# OnOffCircuit.net
KiCad netlist of a schematic drawn in Altium Designer
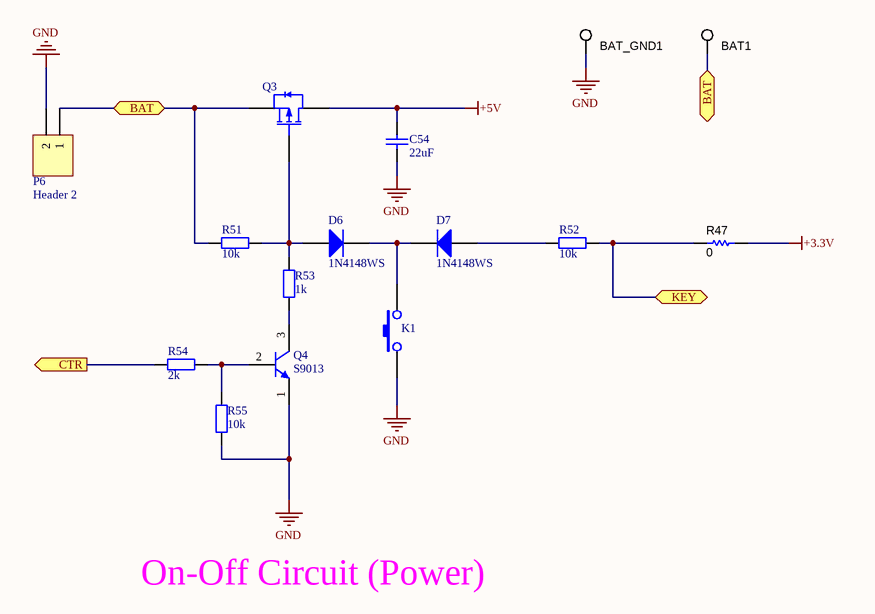
[diagram p0: OnOffCircuit.SchDoc]

(export (version "E")
  (design (tool "Eeschema 10.0.6"))
  (components
    (comp (ref "BAT1")
      (value "5015")
      (footprint "Testpoint_Keystone_Miniature")
      (description "Test Point, Miniature, SMT")
      (fields (field (name "MANUFACTURER") "Keystone") (field (name "PUBLISHER") "Texas Instruments"))
      (libsource (lib "Connectors_Keystone") (part "5015"))
    )
    (comp (ref "BAT_GND1")
      (value "5015")
      (footprint "Testpoint_Keystone_Miniature")
      (description "Test Point, Miniature, SMT")
      (fields (field (name "MANUFACTURER") "Keystone") (field (name "PUBLISHER") "Texas Instruments"))
      (libsource (lib "Connectors_Keystone") (part "5015"))
    )
    (comp (ref "C54")
      (value "22uF")
      (footprint "FDC2214:0603")
      (description "0402贴片电容")
      (libsource (lib "02-Miscellaneous_Devices_ZSF_Library") (part "Cap_0402"))
    )
    (comp (ref "D6")
      (value "1N4148WS")
      (footprint "SOD-323")
      (description "二极管")
      (libsource (lib "02-Miscellaneous_Devices_ZSF_Library") (part "1N4148WS_SOD-323"))
    )
    (comp (ref "D7")
      (value "1N4148WS")
      (footprint "SOD-323")
      (description "二极管")
      (libsource (lib "02-Miscellaneous_Devices_ZSF_Library") (part "1N4148WS_SOD-323"))
    )
    (comp (ref "K1") (value "KEY-2") (footprint "KEY-6*6*9.5") (libsource (lib "KEY") (part "KEY-2")))
    (comp (ref "P6")
      (value "Header 2")
      (footprint "XH254-2")
      (description "Header, 2-Pin")
      (fields (field (name "PUBLISHER") "Altium Limited"))
      (libsource (lib "01-Connect_IntegratedLibrary") (part "Header 2"))
    )
    (comp (ref "Q3")
      (value "AO3401A P道沟 X13A15 SOT-23")
      (footprint "SOT-23-3L")
      (description "MOS(场效应管)")
      (libsource (lib "02-Miscellaneous_Devices_ZSF_Library") (part "AO3401A P道沟 X13A15 SOT-23"))
    )
    (comp (ref "Q4")
      (value "S9013")
      (footprint "SOT-23-3_L2.9-W1.3-P1.90-LS2.4-BR")
      (description "NPN型小功率三极管")
      (libsource (lib "02-Miscellaneous_Devices_ZSF_Library") (part "9013_TO-92"))
    )
    (comp (ref "R47")
      (value "0")
      (footprint "0805_R")
      (description "RES, 0 ohm, 5%, 0.1W, 0603")
      (fields
        (field (name "PARTNUMBER") "CRCW06030000Z0EA")
        (field (name "MANUFACTURER") "Vishay-Dale")
        (field (name "PUBLISHER") "Texas Instruments")
      )
      (libsource (lib "Resistor_0603") (part "CRCW06030000Z0EA"))
    )
    (comp (ref "R51")
      (value "10k")
      (footprint "0805_R")
      (description "0805贴片电阻")
      (libsource (lib "") (part "Res_0805_1"))
    )
    (comp (ref "R52")
      (value "10k")
      (footprint "0805_R")
      (description "0805贴片电阻")
      (libsource (lib "") (part "Res_0805_1"))
    )
    (comp (ref "R53")
      (value "1k")
      (footprint "0805_R")
      (description "0805贴片电阻")
      (libsource (lib "02-Miscellaneous_Devices_ZSF_Library") (part "Res_0805"))
    )
    (comp (ref "R54")
      (value "2k")
      (footprint "0805_R")
      (description "0805贴片电阻")
      (libsource (lib "") (part "Res_0805_2"))
    )
    (comp (ref "R55")
      (value "10k")
      (footprint "0805_R")
      (description "0805贴片电阻")
      (libsource (lib "02-Miscellaneous_Devices_ZSF_Library") (part "Res_0805"))
    )
  )
  (nets
    (net (code "1") (name "+3.3V") (class "Default")
      (node (ref "R47") (pin "2") (pinfunction "2_2") (pintype "passive"))
    )
    (net (code "2") (name "+5V") (class "Default")
      (node (ref "C54") (pin "2") (pinfunction "2_2") (pintype "passive"))
      (node (ref "Q3") (pin "3") (pinfunction "D_3") (pintype "passive"))
    )
    (net (code "3") (name "/BAT") (class "Default")
      (node (ref "BAT1") (pin "1") (pintype "passive"))
      (node (ref "P6") (pin "1") (pinfunction "1_1") (pintype "passive"))
      (node (ref "Q3") (pin "2") (pinfunction "S_2") (pintype "passive"))
      (node (ref "R51") (pin "1") (pinfunction "1_1") (pintype "passive"))
    )
    (net (code "4") (name "/CTR") (class "Default")
      (node (ref "R54") (pin "2") (pinfunction "2_2") (pintype "passive"))
    )
    (net (code "5") (name "/KEY") (class "Default")
      (node (ref "R47") (pin "1") (pinfunction "1_1") (pintype "passive"))
      (node (ref "R52") (pin "2") (pinfunction "2_2") (pintype "passive"))
    )
    (net (code "6") (name "GND") (class "Default")
      (node (ref "BAT_GND1") (pin "1") (pintype "passive"))
      (node (ref "C54") (pin "1") (pinfunction "1_1") (pintype "passive"))
      (node (ref "K1") (pin "1") (pinfunction "1_1") (pintype "passive"))
      (node (ref "P6") (pin "2") (pinfunction "2_2") (pintype "passive"))
      (node (ref "Q4") (pin "1") (pinfunction "E_1") (pintype "passive"))
      (node (ref "R55") (pin "1") (pinfunction "1_1") (pintype "passive"))
    )
    (net (code "7") (name "Net-(D6-A)") (class "Default")
      (node (ref "D6") (pin "1") (pinfunction "A_1") (pintype "passive"))
      (node (ref "Q3") (pin "1") (pinfunction "G_1") (pintype "passive"))
      (node (ref "R51") (pin "2") (pinfunction "2_2") (pintype "passive"))
      (node (ref "R53") (pin "2") (pinfunction "2_2") (pintype "passive"))
    )
    (net (code "8") (name "Net-(D6-K)") (class "Default")
      (node (ref "D6") (pin "2") (pinfunction "K_2") (pintype "passive"))
      (node (ref "D7") (pin "2") (pinfunction "K_2") (pintype "passive"))
      (node (ref "K1") (pin "2") (pinfunction "2_2") (pintype "passive"))
    )
    (net (code "9") (name "Net-(D7-A)") (class "Default")
      (node (ref "D7") (pin "1") (pinfunction "A_1") (pintype "passive"))
      (node (ref "R52") (pin "1") (pinfunction "1_1") (pintype "passive"))
    )
    (net (code "10") (name "Net-(Q4-B)") (class "Default")
      (node (ref "Q4") (pin "2") (pinfunction "B_2") (pintype "passive"))
      (node (ref "R54") (pin "1") (pinfunction "1_1") (pintype "passive"))
      (node (ref "R55") (pin "2") (pinfunction "2_2") (pintype "passive"))
    )
    (net (code "11") (name "Net-(Q4-C)") (class "Default")
      (node (ref "Q4") (pin "3") (pinfunction "C_3") (pintype "passive"))
      (node (ref "R53") (pin "1") (pinfunction "1_1") (pintype "passive"))
    )
  )
)
